# LD_driver.net
KiCad netlist of a schematic drawn in Altium Designer
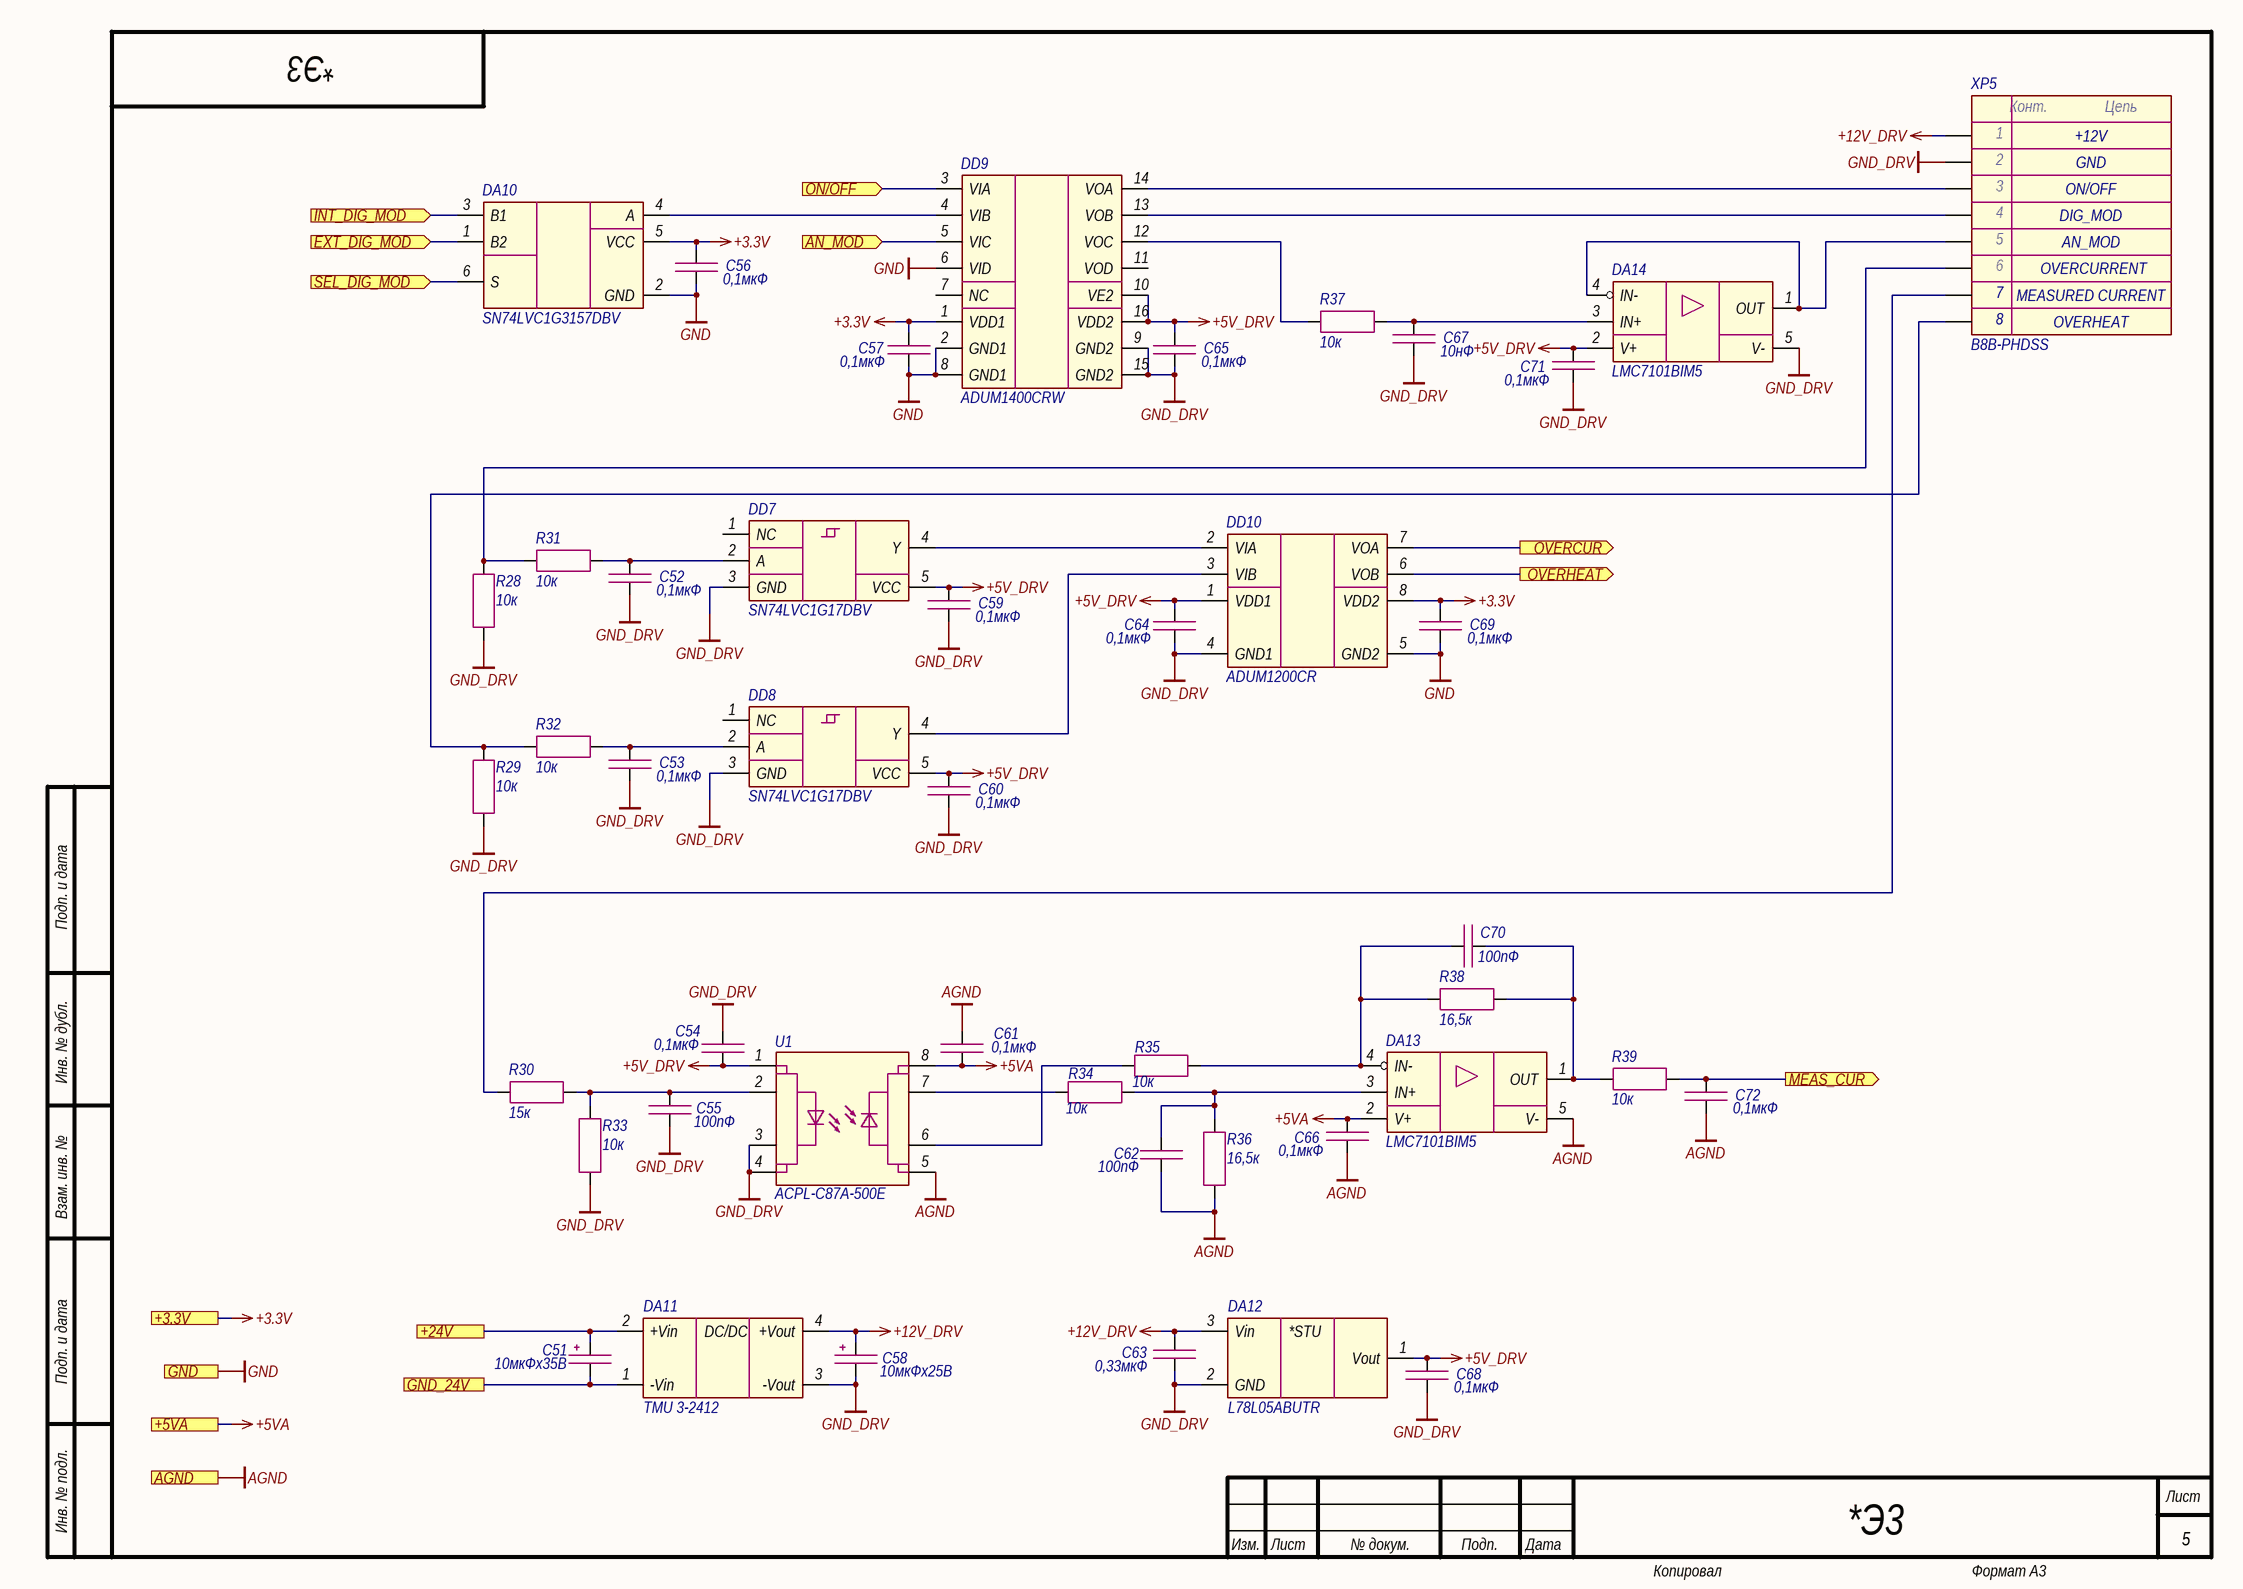
[diagram p0: LD_driver.SchDoc]

(export (version "E")
  (design (tool "Eeschema 10.0.6"))
  (components
    (comp (ref "C51")
      (value "10мкФх35B")
      (footprint "Pcb_library:CAP_C")
      (libsource (lib "Schem_library") (part "Capacitor_Polar"))
    )
    (comp (ref "C52")
      (value "0,1мкФ")
      (footprint "Pcb_library:CAP_0603")
      (fields (field (name "MANUFACTURER") "Murata"))
      (libsource (lib "Schem_library") (part "Capacitor"))
    )
    (comp (ref "C53")
      (value "0,1мкФ")
      (footprint "Pcb_library:CAP_0603")
      (fields (field (name "MANUFACTURER") "Murata"))
      (libsource (lib "Schem_library") (part "Capacitor"))
    )
    (comp (ref "C54")
      (value "0,1мкФ")
      (footprint "Pcb_library:CAP_0603")
      (fields (field (name "MANUFACTURER") "Murata"))
      (libsource (lib "Schem_library") (part "Capacitor"))
    )
    (comp (ref "C55")
      (value "100пФ")
      (footprint "Pcb_library:CAP_0603")
      (fields (field (name "MANUFACTURER") "Murata"))
      (libsource (lib "Schem_library") (part "Capacitor"))
    )
    (comp (ref "C56")
      (value "0,1мкФ")
      (footprint "Pcb_library:CAP_0603")
      (fields (field (name "MANUFACTURER") "Murata"))
      (libsource (lib "Schem_library") (part "Capacitor"))
    )
    (comp (ref "C57")
      (value "0,1мкФ")
      (footprint "Pcb_library:CAP_0603")
      (fields (field (name "MANUFACTURER") "Murata"))
      (libsource (lib "Schem_library") (part "Capacitor"))
    )
    (comp (ref "C58")
      (value "10мкФх25B")
      (footprint "Pcb_library:CAP_B")
      (libsource (lib "Schem_library") (part "Capacitor_Polar"))
    )
    (comp (ref "C59")
      (value "0,1мкФ")
      (footprint "Pcb_library:CAP_0603")
      (fields (field (name "MANUFACTURER") "Murata"))
      (libsource (lib "Schem_library") (part "Capacitor"))
    )
    (comp (ref "C60")
      (value "0,1мкФ")
      (footprint "Pcb_library:CAP_0603")
      (fields (field (name "MANUFACTURER") "Murata"))
      (libsource (lib "Schem_library") (part "Capacitor"))
    )
    (comp (ref "C61")
      (value "0,1мкФ")
      (footprint "Pcb_library:CAP_0603")
      (fields (field (name "MANUFACTURER") "Murata"))
      (libsource (lib "Schem_library") (part "Capacitor"))
    )
    (comp (ref "C62")
      (value "100пФ")
      (footprint "Pcb_library:CAP_0603")
      (fields (field (name "MANUFACTURER") "Murata"))
      (libsource (lib "Schem_library") (part "Capacitor"))
    )
    (comp (ref "C63")
      (value "0,33мкФ")
      (footprint "Pcb_library:CAP_0805")
      (fields (field (name "MANUFACTURER") "Murata"))
      (libsource (lib "Schem_library") (part "Capacitor"))
    )
    (comp (ref "C64")
      (value "0,1мкФ")
      (footprint "Pcb_library:CAP_0603")
      (fields (field (name "MANUFACTURER") "Murata"))
      (libsource (lib "Schem_library") (part "Capacitor"))
    )
    (comp (ref "C65")
      (value "0,1мкФ")
      (footprint "Pcb_library:CAP_0603")
      (fields (field (name "MANUFACTURER") "Murata"))
      (libsource (lib "Schem_library") (part "Capacitor"))
    )
    (comp (ref "C66")
      (value "0,1мкФ")
      (footprint "Pcb_library:CAP_0603")
      (fields (field (name "MANUFACTURER") "Murata"))
      (libsource (lib "Schem_library") (part "Capacitor"))
    )
    (comp (ref "C67")
      (value "10нФ")
      (footprint "Pcb_library:CAP_0603")
      (fields (field (name "MANUFACTURER") "Murata"))
      (libsource (lib "Schem_library") (part "Capacitor"))
    )
    (comp (ref "C68")
      (value "0,1мкФ")
      (footprint "Pcb_library:CAP_0603")
      (fields (field (name "MANUFACTURER") "Murata"))
      (libsource (lib "Schem_library") (part "Capacitor"))
    )
    (comp (ref "C69")
      (value "0,1мкФ")
      (footprint "Pcb_library:CAP_0603")
      (fields (field (name "MANUFACTURER") "Murata"))
      (libsource (lib "Schem_library") (part "Capacitor"))
    )
    (comp (ref "C70")
      (value "100пФ")
      (footprint "Pcb_library:CAP_0603")
      (fields (field (name "MANUFACTURER") "Murata"))
      (libsource (lib "Schem_library") (part "Capacitor"))
    )
    (comp (ref "C71")
      (value "0,1мкФ")
      (footprint "Pcb_library:CAP_0603")
      (fields (field (name "MANUFACTURER") "Murata"))
      (libsource (lib "Schem_library") (part "Capacitor"))
    )
    (comp (ref "C72")
      (value "0,1мкФ")
      (footprint "Pcb_library:CAP_0603")
      (fields (field (name "MANUFACTURER") "Murata"))
      (libsource (lib "Schem_library") (part "Capacitor"))
    )
    (comp (ref "DA10")
      (value "SN74LVC1G3157DBV")
      (footprint "Pcb_library:SOT-23-6")
      (fields (field (name "MANUFACTURER") "Texas Instruments"))
      (libsource (lib "Schem_library") (part "SN74LVC1G3157"))
    )
    (comp (ref "DA11")
      (value "TMU 3-2412")
      (footprint "Pcb_library:TMU3 (SIP-4)")
      (fields (field (name "MANUFACTURER") "Traco Power"))
      (libsource (lib "Schem_library") (part "TMU3"))
    )
    (comp (ref "DA12")
      (value "L78L05ABUTR")
      (footprint "Pcb_library:SOT-89")
      (fields (field (name "MANUFACTURER") "STMicroelectronics"))
      (libsource (lib "Schem_library") (part "LD2981ABU50TR"))
    )
    (comp (ref "DA13")
      (value "LMC7101BIM5")
      (footprint "Pcb_library:SOT-23-5")
      (fields (field (name "MANUFACTURER") "Texas Instruments"))
      (libsource (lib "Schem_library") (part "LMC7101"))
    )
    (comp (ref "DA14")
      (value "LMC7101BIM5")
      (footprint "Pcb_library:SOT-23-5")
      (fields (field (name "MANUFACTURER") "Texas Instruments"))
      (libsource (lib "Schem_library") (part "LMC7101"))
    )
    (comp (ref "DD7")
      (value "SN74LVC1G17DBV")
      (footprint "Pcb_library:SOT-23-5")
      (fields (field (name "MANUFACTURER") "Texas Instruments"))
      (libsource (lib "Schem_library") (part "SN74LVC1G17"))
    )
    (comp (ref "DD8")
      (value "SN74LVC1G17DBV")
      (footprint "Pcb_library:SOT-23-5")
      (fields (field (name "MANUFACTURER") "Texas Instruments"))
      (libsource (lib "Schem_library") (part "SN74LVC1G17"))
    )
    (comp (ref "DD9")
      (value "ADUM1400CRW")
      (footprint "Pcb_library:SOIC-16W")
      (fields (field (name "MANUFACTURER") "Analog Devices"))
      (libsource (lib "Schem_library") (part "ADUM1400"))
    )
    (comp (ref "DD10")
      (value "ADUM1200CR")
      (footprint "Pcb_library:SOIC-8")
      (fields (field (name "MANUFACTURER") "Analog Devices"))
      (libsource (lib "Schem_library") (part "ADUM1200"))
    )
    (comp (ref "R28")
      (value "10к")
      (footprint "Pcb_library:RES_0603")
      (fields (field (name "MANUFACTURER") "Yageo"))
      (libsource (lib "Schem_library") (part "Resistor"))
    )
    (comp (ref "R29")
      (value "10к")
      (footprint "Pcb_library:RES_0603")
      (fields (field (name "MANUFACTURER") "Yageo"))
      (libsource (lib "Schem_library") (part "Resistor"))
    )
    (comp (ref "R30")
      (value "15к")
      (footprint "Pcb_library:RES_0603")
      (fields (field (name "MANUFACTURER") "Yageo"))
      (libsource (lib "Schem_library") (part "Resistor"))
    )
    (comp (ref "R31")
      (value "10к")
      (footprint "Pcb_library:RES_0603")
      (fields (field (name "MANUFACTURER") "Yageo"))
      (libsource (lib "Schem_library") (part "Resistor"))
    )
    (comp (ref "R32")
      (value "10к")
      (footprint "Pcb_library:RES_0603")
      (fields (field (name "MANUFACTURER") "Yageo"))
      (libsource (lib "Schem_library") (part "Resistor"))
    )
    (comp (ref "R33")
      (value "10к")
      (footprint "Pcb_library:RES_0603")
      (fields (field (name "MANUFACTURER") "Yageo"))
      (libsource (lib "Schem_library") (part "Resistor"))
    )
    (comp (ref "R34")
      (value "10к")
      (footprint "Pcb_library:RES_0603")
      (fields (field (name "MANUFACTURER") "Yageo"))
      (libsource (lib "Schem_library") (part "Resistor"))
    )
    (comp (ref "R35")
      (value "10к")
      (footprint "Pcb_library:RES_0603")
      (fields (field (name "MANUFACTURER") "Yageo"))
      (libsource (lib "Schem_library") (part "Resistor"))
    )
    (comp (ref "R36")
      (value "16,5к")
      (footprint "Pcb_library:RES_0603")
      (fields (field (name "MANUFACTURER") "Yageo"))
      (libsource (lib "Schem_library") (part "Resistor"))
    )
    (comp (ref "R37")
      (value "10к")
      (footprint "Pcb_library:RES_0603")
      (fields (field (name "MANUFACTURER") "Yageo"))
      (libsource (lib "Schem_library") (part "Resistor"))
    )
    (comp (ref "R38")
      (value "16,5к")
      (footprint "Pcb_library:RES_0603")
      (fields (field (name "MANUFACTURER") "Yageo"))
      (libsource (lib "Schem_library") (part "Resistor"))
    )
    (comp (ref "R39")
      (value "10к")
      (footprint "Pcb_library:RES_0603")
      (fields (field (name "MANUFACTURER") "Yageo"))
      (libsource (lib "Schem_library") (part "Resistor"))
    )
    (comp (ref "U1")
      (value "ACPL-C87A-500E")
      (footprint "Pcb_library:SSO-8")
      (fields (field (name "MANUFACTURER") "Broadcom"))
      (libsource (lib "Schem_library") (part "ACPL-C87"))
    )
    (comp (ref "XP5")
      (value "B8B-PHDSS")
      (footprint "Pcb_library:B8B-PHDSS")
      (fields (field (name "MANUFACTURER") "JST"))
      (libsource (lib "Schem_library") (part "Connector-8"))
    )
  )
  (nets
    (net (code "1") (name "+3.3V") (class "Default")
      (node (ref "C56") (pin "1") (pinfunction "1_1") (pintype "passive"))
      (node (ref "C57") (pin "1") (pinfunction "1_1") (pintype "passive"))
      (node (ref "C69") (pin "1") (pinfunction "1_1") (pintype "passive"))
      (node (ref "DA10") (pin "5") (pinfunction "VCC_5") (pintype "passive"))
      (node (ref "DD10") (pin "8") (pinfunction "VDD2_8") (pintype "passive"))
      (node (ref "DD9") (pin "1") (pinfunction "VDD1_1") (pintype "passive"))
    )
    (net (code "2") (name "+5VA") (class "Default")
      (node (ref "C61") (pin "1") (pinfunction "1_1") (pintype "passive"))
      (node (ref "C66") (pin "1") (pinfunction "1_1") (pintype "passive"))
      (node (ref "DA13") (pin "2") (pinfunction "V+_2") (pintype "passive"))
      (node (ref "U1") (pin "8") (pinfunction "VDD2_8") (pintype "passive"))
    )
    (net (code "3") (name "+5V_DRV") (class "Default")
      (node (ref "C54") (pin "1") (pinfunction "1_1") (pintype "passive"))
      (node (ref "C59") (pin "1") (pinfunction "1_1") (pintype "passive"))
      (node (ref "C60") (pin "1") (pinfunction "1_1") (pintype "passive"))
      (node (ref "C64") (pin "1") (pinfunction "1_1") (pintype "passive"))
      (node (ref "C65") (pin "1") (pinfunction "1_1") (pintype "passive"))
      (node (ref "C68") (pin "1") (pinfunction "1_1") (pintype "passive"))
      (node (ref "C71") (pin "1") (pinfunction "1_1") (pintype "passive"))
      (node (ref "DA12") (pin "1") (pinfunction "Vout_1") (pintype "passive"))
      (node (ref "DA14") (pin "2") (pinfunction "V+_2") (pintype "passive"))
      (node (ref "DD10") (pin "1") (pinfunction "VDD1_1") (pintype "passive"))
      (node (ref "DD7") (pin "5") (pinfunction "VCC_5") (pintype "passive"))
      (node (ref "DD8") (pin "5") (pinfunction "VCC_5") (pintype "passive"))
      (node (ref "DD9") (pin "10") (pinfunction "VE2_10") (pintype "passive"))
      (node (ref "DD9") (pin "16") (pinfunction "VDD2_16") (pintype "passive"))
      (node (ref "U1") (pin "1") (pinfunction "VDD1_1") (pintype "passive"))
    )
    (net (code "4") (name "+12V_DRV") (class "Default")
      (node (ref "C58") (pin "1") (pinfunction "1_1") (pintype "passive"))
      (node (ref "C63") (pin "2") (pinfunction "2_2") (pintype "passive"))
      (node (ref "DA11") (pin "4") (pinfunction "+Vout_4") (pintype "passive"))
      (node (ref "DA12") (pin "3") (pinfunction "Vin_3") (pintype "passive"))
      (node (ref "XP5") (pin "1") (pintype "passive"))
    )
    (net (code "5") (name "/+24V") (class "Default")
      (node (ref "C51") (pin "1") (pinfunction "1_1") (pintype "passive"))
      (node (ref "DA11") (pin "2") (pinfunction "+Vin_2") (pintype "passive"))
    )
    (net (code "6") (name "/AN_MOD") (class "Default")
      (node (ref "DD9") (pin "5") (pinfunction "VIC_5") (pintype "passive"))
    )
    (net (code "7") (name "/EXT_DIG_MOD") (class "Default")
      (node (ref "DA10") (pin "1") (pinfunction "B2_1") (pintype "passive"))
    )
    (net (code "8") (name "/GND_24V") (class "Default")
      (node (ref "C51") (pin "2") (pinfunction "2_2") (pintype "passive"))
      (node (ref "DA11") (pin "1") (pinfunction "-Vin_1") (pintype "passive"))
    )
    (net (code "9") (name "/INT_DIG_MOD") (class "Default")
      (node (ref "DA10") (pin "3") (pinfunction "B1_3") (pintype "passive"))
    )
    (net (code "10") (name "/MEAS_CUR") (class "Default")
      (node (ref "C72") (pin "1") (pinfunction "1_1") (pintype "passive"))
      (node (ref "R39") (pin "2") (pinfunction "2_2") (pintype "passive"))
    )
    (net (code "11") (name "/ON{slash}OFF") (class "Default")
      (node (ref "DD9") (pin "3") (pinfunction "VIA_3") (pintype "passive"))
    )
    (net (code "12") (name "/OVERCUR") (class "Default")
      (node (ref "DD10") (pin "7") (pinfunction "VOA_7") (pintype "passive"))
    )
    (net (code "13") (name "/OVERHEAT") (class "Default")
      (node (ref "DD10") (pin "6") (pinfunction "VOB_6") (pintype "passive"))
    )
    (net (code "14") (name "/SEL_DIG_MOD") (class "Default")
      (node (ref "DA10") (pin "6") (pinfunction "S_6") (pintype "passive"))
    )
    (net (code "15") (name "AGND") (class "Default")
      (node (ref "C61") (pin "2") (pinfunction "2_2") (pintype "passive"))
      (node (ref "C62") (pin "2") (pinfunction "2_2") (pintype "passive"))
      (node (ref "C66") (pin "2") (pinfunction "2_2") (pintype "passive"))
      (node (ref "C72") (pin "2") (pinfunction "2_2") (pintype "passive"))
      (node (ref "DA13") (pin "5") (pinfunction "V-_5") (pintype "passive"))
      (node (ref "R36") (pin "2") (pinfunction "2_2") (pintype "passive"))
      (node (ref "U1") (pin "5") (pinfunction "GND2_5") (pintype "passive"))
    )
    (net (code "16") (name "GND") (class "Default")
      (node (ref "C56") (pin "2") (pinfunction "2_2") (pintype "passive"))
      (node (ref "C57") (pin "2") (pinfunction "2_2") (pintype "passive"))
      (node (ref "C69") (pin "2") (pinfunction "2_2") (pintype "passive"))
      (node (ref "DA10") (pin "2") (pinfunction "GND_2") (pintype "passive"))
      (node (ref "DD10") (pin "5") (pinfunction "GND2_5") (pintype "passive"))
      (node (ref "DD9") (pin "2") (pinfunction "GND1_2") (pintype "passive"))
      (node (ref "DD9") (pin "6") (pinfunction "VID_6") (pintype "passive"))
      (node (ref "DD9") (pin "8") (pinfunction "GND1_8") (pintype "passive"))
    )
    (net (code "17") (name "GND_DRV") (class "Default")
      (node (ref "C52") (pin "2") (pinfunction "2_2") (pintype "passive"))
      (node (ref "C53") (pin "2") (pinfunction "2_2") (pintype "passive"))
      (node (ref "C54") (pin "2") (pinfunction "2_2") (pintype "passive"))
      (node (ref "C55") (pin "1") (pinfunction "1_1") (pintype "passive"))
      (node (ref "C58") (pin "2") (pinfunction "2_2") (pintype "passive"))
      (node (ref "C59") (pin "2") (pinfunction "2_2") (pintype "passive"))
      (node (ref "C60") (pin "2") (pinfunction "2_2") (pintype "passive"))
      (node (ref "C63") (pin "1") (pinfunction "1_1") (pintype "passive"))
      (node (ref "C64") (pin "2") (pinfunction "2_2") (pintype "passive"))
      (node (ref "C65") (pin "2") (pinfunction "2_2") (pintype "passive"))
      (node (ref "C67") (pin "2") (pinfunction "2_2") (pintype "passive"))
      (node (ref "C68") (pin "2") (pinfunction "2_2") (pintype "passive"))
      (node (ref "C71") (pin "2") (pinfunction "2_2") (pintype "passive"))
      (node (ref "DA11") (pin "3") (pinfunction "-Vout_3") (pintype "passive"))
      (node (ref "DA12") (pin "2") (pinfunction "GND_2") (pintype "passive"))
      (node (ref "DA14") (pin "5") (pinfunction "V-_5") (pintype "passive"))
      (node (ref "DD10") (pin "4") (pinfunction "GND1_4") (pintype "passive"))
      (node (ref "DD7") (pin "3") (pinfunction "GND_3") (pintype "passive"))
      (node (ref "DD8") (pin "3") (pinfunction "GND_3") (pintype "passive"))
      (node (ref "DD9") (pin "15") (pinfunction "GND2_15") (pintype "passive"))
      (node (ref "DD9") (pin "9") (pinfunction "GND2_9") (pintype "passive"))
      (node (ref "R28") (pin "1") (pinfunction "1_1") (pintype "passive"))
      (node (ref "R29") (pin "1") (pinfunction "1_1") (pintype "passive"))
      (node (ref "R33") (pin "2") (pinfunction "2_2") (pintype "passive"))
      (node (ref "U1") (pin "3") (pinfunction "SHDN_3") (pintype "passive"))
      (node (ref "U1") (pin "4") (pinfunction "GND1_4") (pintype "passive"))
      (node (ref "XP5") (pin "2") (pintype "passive"))
    )
    (net (code "18") (name "Net-(DA10-A)") (class "Default")
      (node (ref "DA10") (pin "4") (pinfunction "A_4") (pintype "passive"))
      (node (ref "DD9") (pin "4") (pinfunction "VIB_4") (pintype "passive"))
    )
    (net (code "19") (name "Net-(DA13-IN+)") (class "Default")
      (node (ref "C62") (pin "1") (pinfunction "1_1") (pintype "passive"))
      (node (ref "DA13") (pin "3") (pinfunction "IN+_3") (pintype "passive"))
      (node (ref "R34") (pin "2") (pinfunction "2_2") (pintype "passive"))
      (node (ref "R36") (pin "1") (pinfunction "1_1") (pintype "passive"))
    )
    (net (code "20") (name "Net-(DA13-IN-)") (class "Default")
      (node (ref "C70") (pin "1") (pinfunction "1_1") (pintype "passive"))
      (node (ref "DA13") (pin "4") (pinfunction "IN-_4") (pintype "passive"))
      (node (ref "R35") (pin "2") (pinfunction "2_2") (pintype "passive"))
      (node (ref "R38") (pin "2") (pinfunction "2_2") (pintype "passive"))
    )
    (net (code "21") (name "Net-(DA13-OUT)") (class "Default")
      (node (ref "C70") (pin "2") (pinfunction "2_2") (pintype "passive"))
      (node (ref "DA13") (pin "1") (pinfunction "OUT_1") (pintype "passive"))
      (node (ref "R38") (pin "1") (pinfunction "1_1") (pintype "passive"))
      (node (ref "R39") (pin "1") (pinfunction "1_1") (pintype "passive"))
    )
    (net (code "22") (name "Net-(DA14-IN+)") (class "Default")
      (node (ref "C67") (pin "1") (pinfunction "1_1") (pintype "passive"))
      (node (ref "DA14") (pin "3") (pinfunction "IN+_3") (pintype "passive"))
      (node (ref "R37") (pin "2") (pinfunction "2_2") (pintype "passive"))
    )
    (net (code "23") (name "Net-(DA14-IN-)") (class "Default")
      (node (ref "DA14") (pin "1") (pinfunction "OUT_1") (pintype "passive"))
      (node (ref "DA14") (pin "4") (pinfunction "IN-_4") (pintype "passive"))
      (node (ref "XP5") (pin "5") (pintype "passive"))
    )
    (net (code "24") (name "Net-(DD7-A)") (class "Default")
      (node (ref "C52") (pin "1") (pinfunction "1_1") (pintype "passive"))
      (node (ref "DD7") (pin "2") (pinfunction "A_2") (pintype "passive"))
      (node (ref "R31") (pin "2") (pinfunction "2_2") (pintype "passive"))
    )
    (net (code "25") (name "Net-(DD8-A)") (class "Default")
      (node (ref "C53") (pin "1") (pinfunction "1_1") (pintype "passive"))
      (node (ref "DD8") (pin "2") (pinfunction "A_2") (pintype "passive"))
      (node (ref "R32") (pin "2") (pinfunction "2_2") (pintype "passive"))
    )
    (net (code "26") (name "Net-(DD9-VOA)") (class "Default")
      (node (ref "DD9") (pin "14") (pinfunction "VOA_14") (pintype "passive"))
      (node (ref "XP5") (pin "3") (pintype "passive"))
    )
    (net (code "27") (name "Net-(DD9-VOB)") (class "Default")
      (node (ref "DD9") (pin "13") (pinfunction "VOB_13") (pintype "passive"))
      (node (ref "XP5") (pin "4") (pintype "passive"))
    )
    (net (code "28") (name "Net-(DD9-VOC)") (class "Default")
      (node (ref "DD9") (pin "12") (pinfunction "VOC_12") (pintype "passive"))
      (node (ref "R37") (pin "1") (pinfunction "1_1") (pintype "passive"))
    )
    (net (code "29") (name "Net-(DD10-VIA)") (class "Default")
      (node (ref "DD10") (pin "2") (pinfunction "VIA_2") (pintype "passive"))
      (node (ref "DD7") (pin "4") (pinfunction "Y_4") (pintype "passive"))
    )
    (net (code "30") (name "Net-(DD10-VIB)") (class "Default")
      (node (ref "DD10") (pin "3") (pinfunction "VIB_3") (pintype "passive"))
      (node (ref "DD8") (pin "4") (pinfunction "Y_4") (pintype "passive"))
    )
    (net (code "31") (name "Net-(R28-Pad2)") (class "Default")
      (node (ref "R28") (pin "2") (pinfunction "2_2") (pintype "passive"))
      (node (ref "R31") (pin "1") (pinfunction "1_1") (pintype "passive"))
      (node (ref "XP5") (pin "6") (pintype "passive"))
    )
    (net (code "32") (name "Net-(R29-Pad2)") (class "Default")
      (node (ref "R29") (pin "2") (pinfunction "2_2") (pintype "passive"))
      (node (ref "R32") (pin "1") (pinfunction "1_1") (pintype "passive"))
      (node (ref "XP5") (pin "8") (pintype "passive"))
    )
    (net (code "33") (name "Net-(R30-Pad2)") (class "Default")
      (node (ref "R30") (pin "2") (pinfunction "2_2") (pintype "passive"))
      (node (ref "XP5") (pin "7") (pintype "passive"))
    )
    (net (code "34") (name "Net-(U1-VIN)") (class "Default")
      (node (ref "C55") (pin "2") (pinfunction "2_2") (pintype "passive"))
      (node (ref "R30") (pin "1") (pinfunction "1_1") (pintype "passive"))
      (node (ref "R33") (pin "1") (pinfunction "1_1") (pintype "passive"))
      (node (ref "U1") (pin "2") (pinfunction "VIN_2") (pintype "passive"))
    )
    (net (code "35") (name "Net-(U1-VOUT+)") (class "Default")
      (node (ref "R34") (pin "1") (pinfunction "1_1") (pintype "passive"))
      (node (ref "U1") (pin "7") (pinfunction "VOUT+_7") (pintype "passive"))
    )
    (net (code "36") (name "Net-(U1-VOUT-)") (class "Default")
      (node (ref "R35") (pin "1") (pinfunction "1_1") (pintype "passive"))
      (node (ref "U1") (pin "6") (pinfunction "VOUT-_6") (pintype "passive"))
    )
    (net (code "37") (name "unconnected-(DD7-NC-Pad1)") (class "Default")
      (node (ref "DD7") (pin "1") (pinfunction "NC_1") (pintype "passive"))
    )
    (net (code "38") (name "unconnected-(DD8-NC-Pad1)") (class "Default")
      (node (ref "DD8") (pin "1") (pinfunction "NC_1") (pintype "passive"))
    )
    (net (code "39") (name "unconnected-(DD9-NC-Pad7)") (class "Default")
      (node (ref "DD9") (pin "7") (pinfunction "NC_7") (pintype "passive"))
    )
    (net (code "40") (name "unconnected-(DD9-VOD-Pad11)") (class "Default")
      (node (ref "DD9") (pin "11") (pinfunction "VOD_11") (pintype "passive"))
    )
  )
)
